# 7segement4minidigits1badidea-mk-3.net
KiCad netlist of a schematic drawn in EAGLE
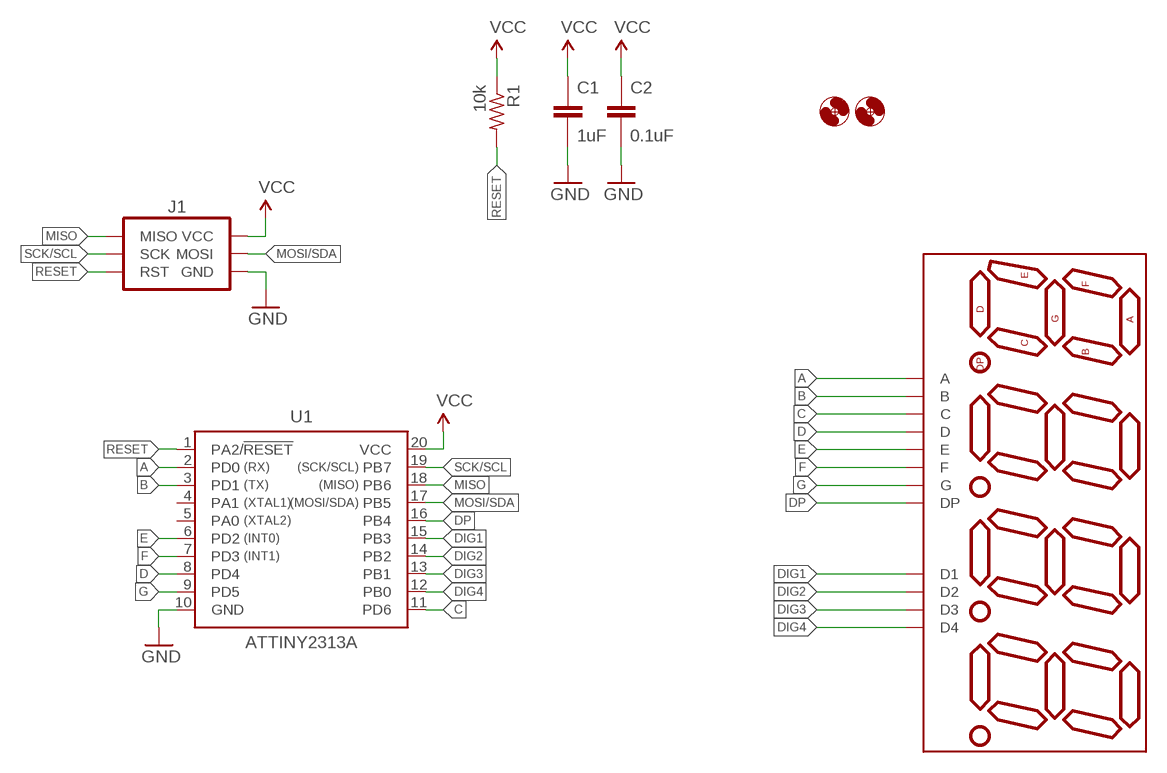
[diagram p0: schematic, sheet 1]

(export (version "E")
  (design (tool "Eeschema 10.0.6"))
  (components
    (comp (ref "BUBBLES!")
      (value "(>^_^)>")
      (footprint "eagle-import:DIP12-SMD-WAT")
      (libsource (lib "eagle-import") (part "7-SEGMENT-4DIGIT-COUNTERWAT"))
    )
    (comp (ref "C1")
      (value "1uF")
      (footprint "eagle-import:C0805")
      (libsource (lib "eagle-import") (part "CAPACITOR-CERAMICC0805"))
    )
    (comp (ref "C2")
      (value "0.1uF")
      (footprint "eagle-import:C0603")
      (libsource (lib "eagle-import") (part "CAPACITOR-CERAMICC0603"))
    )
    (comp (ref "H1")
      (value "HOLE#2")
      (footprint "eagle-import:HOLE-#2")
      (libsource (lib "eagle-import") (part "HOLE#2"))
    )
    (comp (ref "H2")
      (value "HOLE#2")
      (footprint "eagle-import:HOLE-#2")
      (libsource (lib "eagle-import") (part "HOLE#2"))
    )
    (comp (ref "J1")
      (value "AVR_SPI_PRG_6PTH_INLINE_I2C")
      (footprint "eagle-import:AVR_ISP_INLINE_PTH_I2C")
      (libsource (lib "eagle-import") (part "AVR_SPI_PRG_6PTH_INLINE_I2C"))
    )
    (comp (ref "R1")
      (value "10k")
      (footprint "eagle-import:R0603")
      (libsource (lib "eagle-import") (part "RESISTORR0603"))
    )
    (comp (ref "U1")
      (value "ATTINY2313A")
      (footprint "eagle-import:SOP20W")
      (libsource (lib "eagle-import") (part "ATTINY2313ASOIC"))
    )
  )
  (nets
    (net (code "1") (name "A") (class "Default")
      (node (ref "BUBBLES!") (pin "12") (pinfunction "A_12") (pintype "bidirectional"))
      (node (ref "U1") (pin "2") (pinfunction "PD0_2") (pintype "bidirectional"))
    )
    (net (code "2") (name "B") (class "Default")
      (node (ref "BUBBLES!") (pin "11") (pinfunction "B_11") (pintype "bidirectional"))
      (node (ref "U1") (pin "3") (pinfunction "PD1_3") (pintype "bidirectional"))
    )
    (net (code "3") (name "C") (class "Default")
      (node (ref "BUBBLES!") (pin "3") (pinfunction "C_3") (pintype "bidirectional"))
      (node (ref "U1") (pin "11") (pinfunction "PD6_11") (pintype "bidirectional"))
    )
    (net (code "4") (name "D") (class "Default")
      (node (ref "BUBBLES!") (pin "8") (pinfunction "D_8") (pintype "bidirectional"))
      (node (ref "U1") (pin "8") (pinfunction "PD4_8") (pintype "bidirectional"))
    )
    (net (code "5") (name "DIG1") (class "Default")
      (node (ref "BUBBLES!") (pin "1") (pinfunction "D1_1") (pintype "bidirectional"))
      (node (ref "U1") (pin "15") (pinfunction "PB3_15") (pintype "bidirectional"))
    )
    (net (code "6") (name "DIG2") (class "Default")
      (node (ref "BUBBLES!") (pin "10") (pinfunction "D2_10") (pintype "bidirectional"))
      (node (ref "U1") (pin "14") (pinfunction "PB2_14") (pintype "bidirectional"))
    )
    (net (code "7") (name "DIG3") (class "Default")
      (node (ref "BUBBLES!") (pin "4") (pinfunction "D3_4") (pintype "bidirectional"))
      (node (ref "U1") (pin "13") (pinfunction "PB1_13") (pintype "bidirectional"))
    )
    (net (code "8") (name "DIG4") (class "Default")
      (node (ref "BUBBLES!") (pin "6") (pinfunction "D4_6") (pintype "bidirectional"))
      (node (ref "U1") (pin "12") (pinfunction "PB0_12") (pintype "bidirectional"))
    )
    (net (code "9") (name "DP") (class "Default")
      (node (ref "BUBBLES!") (pin "5") (pinfunction "DP_5") (pintype "bidirectional"))
      (node (ref "U1") (pin "16") (pinfunction "PB4_16") (pintype "bidirectional"))
    )
    (net (code "10") (name "E") (class "Default")
      (node (ref "BUBBLES!") (pin "2") (pinfunction "E_2") (pintype "bidirectional"))
      (node (ref "U1") (pin "6") (pinfunction "PD2_6") (pintype "bidirectional"))
    )
    (net (code "11") (name "F") (class "Default")
      (node (ref "BUBBLES!") (pin "9") (pinfunction "F_9") (pintype "bidirectional"))
      (node (ref "U1") (pin "7") (pinfunction "PD3_7") (pintype "bidirectional"))
    )
    (net (code "12") (name "G") (class "Default")
      (node (ref "BUBBLES!") (pin "7") (pinfunction "G_7") (pintype "bidirectional"))
      (node (ref "U1") (pin "9") (pinfunction "PD5_9") (pintype "bidirectional"))
    )
    (net (code "13") (name "GND") (class "Default")
      (node (ref "C1") (pin "2") (pinfunction "2_2") (pintype "passive"))
      (node (ref "C2") (pin "2") (pinfunction "2_2") (pintype "passive"))
      (node (ref "J1") (pin "GND") (pinfunction "GND_GND") (pintype "passive"))
      (node (ref "U1") (pin "10") (pinfunction "GND_10") (pintype "bidirectional"))
    )
    (net (code "14") (name "MISO") (class "Default")
      (node (ref "J1") (pin "MISO") (pinfunction "MISO_MISO") (pintype "passive"))
      (node (ref "U1") (pin "18") (pinfunction "PB6_18") (pintype "bidirectional"))
    )
    (net (code "15") (name "MOSI{slash}SDA") (class "Default")
      (node (ref "J1") (pin "MOSI") (pinfunction "MOSI_MOSI") (pintype "passive"))
      (node (ref "U1") (pin "17") (pinfunction "PB5_17") (pintype "bidirectional"))
    )
    (net (code "16") (name "RESET") (class "Default")
      (node (ref "J1") (pin "RESET") (pinfunction "RST_RESET") (pintype "passive"))
      (node (ref "R1") (pin "2") (pinfunction "2_2") (pintype "passive"))
      (node (ref "U1") (pin "1") (pinfunction "PA2/~{RESET}_1") (pintype "bidirectional"))
    )
    (net (code "17") (name "SCK{slash}SCL") (class "Default")
      (node (ref "J1") (pin "SCK") (pinfunction "SCK_SCK") (pintype "passive"))
      (node (ref "U1") (pin "19") (pinfunction "PB7_19") (pintype "bidirectional"))
    )
    (net (code "18") (name "VCC") (class "Default")
      (node (ref "C1") (pin "1") (pinfunction "1_1") (pintype "passive"))
      (node (ref "C2") (pin "1") (pinfunction "1_1") (pintype "passive"))
      (node (ref "J1") (pin "VCC") (pinfunction "VCC_VCC") (pintype "passive"))
      (node (ref "R1") (pin "1") (pinfunction "1_1") (pintype "passive"))
      (node (ref "U1") (pin "20") (pinfunction "VCC_20") (pintype "bidirectional"))
    )
    (net (code "19") (name "unconnected-(U1-PA0-Pad5)") (class "Default")
      (node (ref "U1") (pin "5") (pinfunction "PA0_5") (pintype "bidirectional"))
    )
    (net (code "20") (name "unconnected-(U1-PA1-Pad4)") (class "Default")
      (node (ref "U1") (pin "4") (pinfunction "PA1_4") (pintype "bidirectional"))
    )
  )
)
